# 1_POWER.net
KiCad netlist of a schematic drawn in Altium Designer
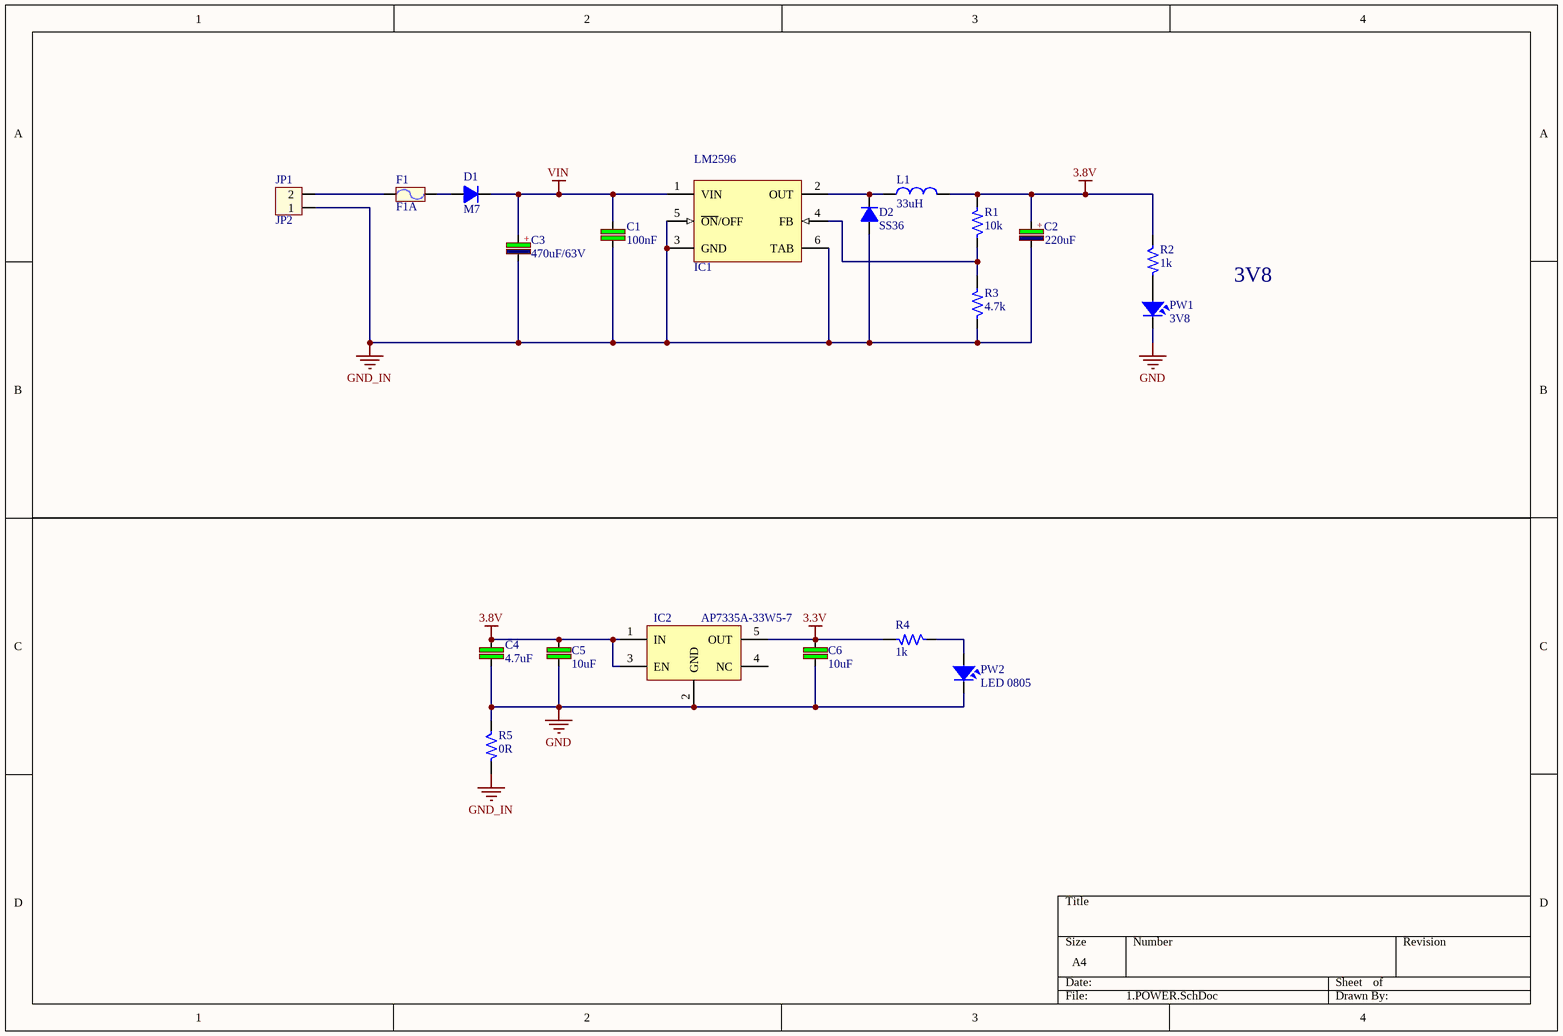
[diagram p0: 1.POWER.SchDoc]

(export (version "E")
  (design (tool "Eeschema 10.0.6"))
  (components
    (comp (ref "C1")
      (value "100nF")
      (footprint "C-0805")
      (description "4.7µF ±10% 35V Ceramic Capacitor X5R 0805 (2012 Metric)")
      (fields
        (field (name "MANUFACTURER") "Samsung Electro-Mechanics")
        (field (name "PART NUMBER") "CL21A475KLCLQNC")
      )
      (libsource (lib "") (part "C_1"))
    )
    (comp (ref "C2")
      (value "220uF")
      (footprint "EEFSDE")
      (description "220µF Molded Tantalum Polymer Capacitor 16V 2917 (7343 Metric) 40mOhm @ 100kHz")
      (fields
        (field (name "MANUFACTURER") "AVX Corporation")
        (field (name "PART NUMBER") "TCME227M016R0040E")
      )
      (libsource (lib "Anh_Trung") (part "CP5"))
    )
    (comp (ref "C3")
      (value "470uF/63V")
      (footprint "CAP-ALU-SMD-C")
      (description "Cap 470uF/63V")
      (libsource (lib "Main") (part "CP3"))
    )
    (comp (ref "C4")
      (value "4.7uF")
      (footprint "C-0805")
      (description "4.7µF ±10% 35V Ceramic Capacitor X5R 0805 (2012 Metric)")
      (fields
        (field (name "MANUFACTURER") "Samsung Electro-Mechanics")
        (field (name "PART NUMBER") "CL21A475KLCLQNC")
      )
      (libsource (lib "") (part "C_1"))
    )
    (comp (ref "C5")
      (value "10uF")
      (footprint "C-0805")
      (description "Cap SMD")
      (fields
        (field (name "MANUFACTURER") "Samsung Electro-Mechanics")
        (field (name "PART NUMBER") "CL21A106KPFNNNG")
      )
      (libsource (lib "Anh_Trung") (part "C"))
    )
    (comp (ref "C6")
      (value "10uF")
      (footprint "C-0805")
      (description "Cap SMD")
      (fields
        (field (name "MANUFACTURER") "Samsung Electro-Mechanics")
        (field (name "PART NUMBER") "CL21A106KPFNNNG")
      )
      (libsource (lib "Anh_Trung") (part "C"))
    )
    (comp (ref "D1")
      (value "M7")
      (footprint "LED-0805-Blue")
      (description "Diode 1A")
      (libsource (lib "Main") (part "D1A"))
    )
    (comp (ref "D2")
      (value "SS36")
      (footprint "LED-0805-Blue")
      (description "Diode Schottky 40V 3A Surface Mount DO-214AC (SMA)")
      (fields
        (field (name "MANUFACTURER") "Vishay General Semiconductor - Diodes Division")
        (field (name "PART NUMBER") "B340A-M3/61T")
      )
      (libsource (lib "Main") (part "B340A"))
    )
    (comp (ref "F1")
      (value "F1A")
      (footprint "Fuse3")
      (description "Fuse")
      (libsource (lib "Anh_Trung") (part "Fuse"))
    )
    (comp (ref "IC1")
      (value "LM2596")
      (footprint "TO-263")
      (description "LM2576")
      (libsource (lib "Main") (part "LM2576"))
    )
    (comp (ref "IC2")
      (value "AP7335A-33W5-7")
      (footprint "SOT23-5")
      (libsource (lib "Anh_Trung") (part "AP7335A-33W5-7"))
    )
    (comp (ref "JP1")
      (value "JP2")
      (footprint "KF2-5.08")
      (description "Connector 2")
      (libsource (lib "Anh_Trung") (part "Con2"))
    )
    (comp (ref "L1")
      (value "33uH")
      (footprint "Inductor_SMD")
      (description "22µH Shielded Inductor 1.65A 96mOhm Max Nonstandard")
      (fields (field (name "MANUFACTURER") "Bourns Inc.") (field (name "PART NUMBER") "SRR0745A-220M"))
      (libsource (lib "Main") (part "L1"))
    )
    (comp (ref "PW1")
      (value "3V8")
      (footprint "LED-0805-Blue")
      (description "LED RED DIFFUSED 0805 SMD")
      (fields
        (field (name "MANUFACTURER") "OSRAM Opto Semiconductors Inc.")
        (field (name "PART NUMBER") "LS R976-NR-1")
      )
      (libsource (lib "Anh_Trung") (part "LED"))
    )
    (comp (ref "PW2")
      (value "LED 0805")
      (footprint "LED-0805-Blue")
      (description "LED RED DIFFUSED 0805 SMD")
      (fields
        (field (name "MANUFACTURER") "OSRAM Opto Semiconductors Inc.")
        (field (name "PART NUMBER") "LS R976-NR-1")
      )
      (libsource (lib "Main") (part "LED"))
    )
    (comp (ref "R1")
      (value "10k")
      (footprint "R-0805")
      (description "RES SMD 10K OHM 1% 1/8W 0805")
      (fields (field (name "MANUFACTURER") "Yageo") (field (name "PART NUMBER") "RC0805FR-0710KL"))
      (libsource (lib "Anh_Trung") (part "R"))
    )
    (comp (ref "R2")
      (value "1k")
      (footprint "R-0805")
      (description "Resistor 1/4W")
      (fields (field (name "MANUFACTURER") "Yageo") (field (name "PART NUMBER") "RC0805FR-071KL"))
      (libsource (lib "Anh_Trung") (part "R"))
    )
    (comp (ref "R3")
      (value "4.7k")
      (footprint "R-0805")
      (description "RES SMD 3.3K OHM 1% 1/8W 0805")
      (fields (field (name "MANUFACTURER") "Yageo") (field (name "PART NUMBER") "RC0805FR-073K3L"))
      (libsource (lib "Anh_Trung") (part "R"))
    )
    (comp (ref "R4")
      (value "1k")
      (footprint "R-0805")
      (description "Resistor 1/4W")
      (fields (field (name "MANUFACTURER") "Yageo") (field (name "PART NUMBER") "RC0805FR-071KL"))
      (libsource (lib "Anh_Trung") (part "R"))
    )
    (comp (ref "R5")
      (value "0R")
      (footprint "R-0805")
      (description "Resistor 1/4W")
      (fields (field (name "MANUFACTURER") "Yageo") (field (name "PART NUMBER") "RC0805FR-071KL"))
      (libsource (lib "Anh_Trung") (part "R"))
    )
  )
  (nets
    (net (code "1") (name "3.3V") (class "Default")
      (node (ref "C6") (pin "1") (pinfunction "1_1") (pintype "passive"))
      (node (ref "IC2") (pin "5") (pinfunction "OUT_5") (pintype "passive"))
      (node (ref "R4") (pin "2") (pinfunction "2_2") (pintype "passive"))
    )
    (net (code "2") (name "3.8V") (class "Default")
      (node (ref "C2") (pin "1") (pinfunction "1_1") (pintype "passive"))
      (node (ref "C4") (pin "2") (pinfunction "2_2") (pintype "passive"))
      (node (ref "C5") (pin "1") (pinfunction "1_1") (pintype "passive"))
      (node (ref "IC2") (pin "1") (pinfunction "IN_1") (pintype "passive"))
      (node (ref "IC2") (pin "3") (pinfunction "EN_3") (pintype "passive"))
      (node (ref "L1") (pin "2") (pinfunction "2_2") (pintype "passive"))
      (node (ref "R1") (pin "2") (pinfunction "2_2") (pintype "passive"))
      (node (ref "R2") (pin "1") (pinfunction "1_1") (pintype "passive"))
    )
    (net (code "3") (name "GND") (class "Default")
      (node (ref "C4") (pin "1") (pinfunction "1_1") (pintype "passive"))
      (node (ref "C5") (pin "2") (pinfunction "2_2") (pintype "passive"))
      (node (ref "C6") (pin "2") (pinfunction "2_2") (pintype "passive"))
      (node (ref "IC2") (pin "2") (pinfunction "GND_2") (pintype "passive"))
      (node (ref "PW1") (pin "2") (pinfunction "2_2") (pintype "passive"))
      (node (ref "PW2") (pin "2") (pinfunction "2_2") (pintype "passive"))
      (node (ref "R5") (pin "1") (pinfunction "1_1") (pintype "passive"))
    )
    (net (code "4") (name "GND_IN") (class "Default")
      (node (ref "C1") (pin "1") (pinfunction "1_1") (pintype "passive"))
      (node (ref "C2") (pin "2") (pinfunction "2_2") (pintype "passive"))
      (node (ref "C3") (pin "2") (pinfunction "2_2") (pintype "passive"))
      (node (ref "D2") (pin "1") (pinfunction "A_1") (pintype "passive"))
      (node (ref "IC1") (pin "3") (pinfunction "GND_3") (pintype "power_in"))
      (node (ref "IC1") (pin "5") (pinfunction "~{ON}/OFF_5") (pintype "input"))
      (node (ref "IC1") (pin "6") (pinfunction "TAB_6") (pintype "power_in"))
      (node (ref "JP1") (pin "1") (pinfunction "1_1") (pintype "passive"))
      (node (ref "R3") (pin "1") (pinfunction "1_1") (pintype "passive"))
      (node (ref "R5") (pin "2") (pinfunction "2_2") (pintype "passive"))
    )
    (net (code "5") (name "Net-(D1-A)") (class "Default")
      (node (ref "D1") (pin "1") (pinfunction "A_1") (pintype "passive"))
      (node (ref "F1") (pin "2") (pinfunction "2_2") (pintype "passive"))
    )
    (net (code "6") (name "Net-(D2-K)") (class "Default")
      (node (ref "D2") (pin "2") (pinfunction "K_2") (pintype "passive"))
      (node (ref "IC1") (pin "2") (pinfunction "OUT_2") (pintype "power_in"))
      (node (ref "L1") (pin "1") (pinfunction "1_1") (pintype "passive"))
    )
    (net (code "7") (name "Net-(F1-Pad1)") (class "Default")
      (node (ref "F1") (pin "1") (pinfunction "1_1") (pintype "passive"))
      (node (ref "JP1") (pin "2") (pinfunction "2_2") (pintype "passive"))
    )
    (net (code "8") (name "Net-(IC1-FB)") (class "Default")
      (node (ref "IC1") (pin "4") (pinfunction "FB_4") (pintype "input"))
      (node (ref "R1") (pin "1") (pinfunction "1_1") (pintype "passive"))
      (node (ref "R3") (pin "2") (pinfunction "2_2") (pintype "passive"))
    )
    (net (code "9") (name "Net-(PW1-Pad1)") (class "Default")
      (node (ref "PW1") (pin "1") (pinfunction "1_1") (pintype "passive"))
      (node (ref "R2") (pin "2") (pinfunction "2_2") (pintype "passive"))
    )
    (net (code "10") (name "Net-(PW2-Pad1)") (class "Default")
      (node (ref "PW2") (pin "1") (pinfunction "1_1") (pintype "passive"))
      (node (ref "R4") (pin "1") (pinfunction "1_1") (pintype "passive"))
    )
    (net (code "11") (name "VIN") (class "Default")
      (node (ref "C1") (pin "2") (pinfunction "2_2") (pintype "passive"))
      (node (ref "C3") (pin "1") (pinfunction "1_1") (pintype "passive"))
      (node (ref "D1") (pin "2") (pinfunction "K_2") (pintype "passive"))
      (node (ref "IC1") (pin "1") (pinfunction "VIN_1") (pintype "power_in"))
    )
    (net (code "12") (name "unconnected-(IC2-NC-Pad4)") (class "Default")
      (node (ref "IC2") (pin "4") (pinfunction "NC_4") (pintype "passive"))
    )
  )
)
